# electrophy_RHD.net
KiCad netlist of a schematic drawn in EAGLE
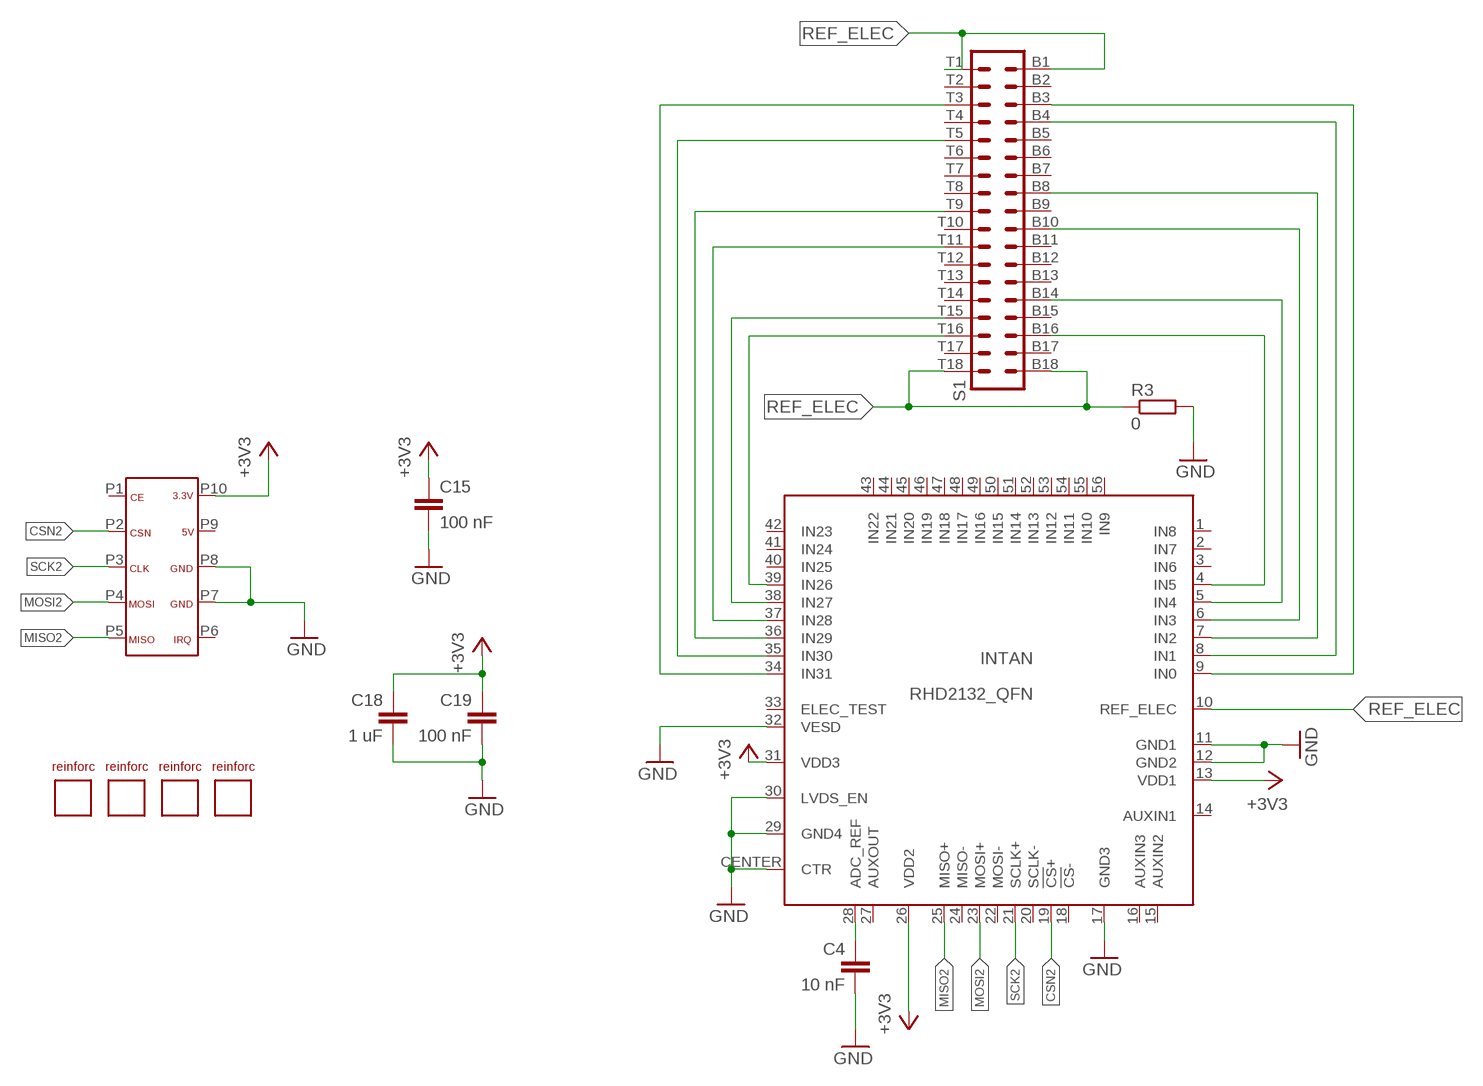
[diagram p0: schematic, sheet 1]

(export (version "E")
  (design (tool "Eeschema 10.0.6"))
  (components
    (comp (ref "C4")
      (value "10 nF")
      (footprint "eagle-import:C0603")
      (libsource (lib "eagle-import") (part "C-EUC0603"))
    )
    (comp (ref "C15")
      (value "100 nF")
      (footprint "eagle-import:C0603")
      (libsource (lib "eagle-import") (part "C-EUC0603"))
    )
    (comp (ref "C18")
      (value "1 uF")
      (footprint "eagle-import:C0603")
      (libsource (lib "eagle-import") (part "C-EUC0603"))
    )
    (comp (ref "C19")
      (value "100 nF")
      (footprint "eagle-import:C0603")
      (libsource (lib "eagle-import") (part "C-EUC0603"))
    )
    (comp (ref "INTAN")
      (value "RHD2132_QFN")
      (footprint "eagle-import:QFN56_8_X_8_LARGE")
      (libsource (lib "eagle-import") (part "RHD2132_QFN"))
    )
    (comp (ref "R3")
      (value "0")
      (footprint "eagle-import:R0603")
      (libsource (lib "eagle-import") (part "R-EU_R0603"))
    )
    (comp (ref "S1")
      (value "OMNETICS_A79027")
      (footprint "eagle-import:OMNETICS_A79027")
      (libsource (lib "eagle-import") (part "OMNETICS_A79027"))
    )
    (comp (ref "U$1")
      (value "DF12-10-FEMALE")
      (footprint "eagle-import:DF12-10-FEMALE")
      (libsource (lib "eagle-import") (part "DF12-10-FEMALE"))
    )
    (comp (ref "U$2")
      (value "REINFORCEMENT")
      (footprint "eagle-import:REINFORCEMENT")
      (libsource (lib "eagle-import") (part "REINFORCEMENT"))
    )
    (comp (ref "U$3")
      (value "REINFORCEMENT")
      (footprint "eagle-import:REINFORCEMENT")
      (libsource (lib "eagle-import") (part "REINFORCEMENT"))
    )
    (comp (ref "U$4")
      (value "REINFORCEMENT")
      (footprint "eagle-import:REINFORCEMENT")
      (libsource (lib "eagle-import") (part "REINFORCEMENT"))
    )
    (comp (ref "U$5")
      (value "REINFORCEMENT")
      (footprint "eagle-import:REINFORCEMENT")
      (libsource (lib "eagle-import") (part "REINFORCEMENT"))
    )
  )
  (nets
    (net (code "1") (name "+3V3") (class "Default")
      (node (ref "C15") (pin "1") (pinfunction "1_1") (pintype "passive"))
      (node (ref "C18") (pin "1") (pinfunction "1_1") (pintype "passive"))
      (node (ref "C19") (pin "1") (pinfunction "1_1") (pintype "passive"))
      (node (ref "INTAN") (pin "13") (pinfunction "VDD1_13") (pintype "bidirectional"))
      (node (ref "INTAN") (pin "26") (pinfunction "VDD2_26") (pintype "bidirectional"))
      (node (ref "INTAN") (pin "31") (pinfunction "VDD3_31") (pintype "bidirectional"))
      (node (ref "U$1") (pin "P10") (pinfunction "P10_P10") (pintype "passive"))
    )
    (net (code "2") (name "CSN2") (class "Default")
      (node (ref "INTAN") (pin "19") (pinfunction "~{CS}+_19") (pintype "bidirectional"))
      (node (ref "U$1") (pin "P2") (pinfunction "P2_P2") (pintype "passive"))
    )
    (net (code "3") (name "GND") (class "Default")
      (node (ref "C15") (pin "2") (pinfunction "2_2") (pintype "passive"))
      (node (ref "C18") (pin "2") (pinfunction "2_2") (pintype "passive"))
      (node (ref "C19") (pin "2") (pinfunction "2_2") (pintype "passive"))
      (node (ref "C4") (pin "2") (pinfunction "2_2") (pintype "passive"))
      (node (ref "INTAN") (pin "11") (pinfunction "GND1_11") (pintype "bidirectional"))
      (node (ref "INTAN") (pin "12") (pinfunction "GND2_12") (pintype "bidirectional"))
      (node (ref "INTAN") (pin "17") (pinfunction "GND3_17") (pintype "bidirectional"))
      (node (ref "INTAN") (pin "29") (pinfunction "GND4_29") (pintype "bidirectional"))
      (node (ref "INTAN") (pin "30") (pinfunction "LVDS_EN_30") (pintype "bidirectional"))
      (node (ref "INTAN") (pin "32") (pinfunction "VESD_32") (pintype "bidirectional"))
      (node (ref "INTAN") (pin "CENTER") (pinfunction "CTR_CENTER") (pintype "bidirectional"))
      (node (ref "R3") (pin "2") (pinfunction "2_2") (pintype "passive"))
      (node (ref "U$1") (pin "P7") (pinfunction "P7_P7") (pintype "passive"))
      (node (ref "U$1") (pin "P8") (pinfunction "P8_P8") (pintype "passive"))
    )
    (net (code "4") (name "MISO2") (class "Default")
      (node (ref "INTAN") (pin "25") (pinfunction "MISO+_25") (pintype "bidirectional"))
      (node (ref "U$1") (pin "P5") (pinfunction "P5_P5") (pintype "passive"))
    )
    (net (code "5") (name "MOSI2") (class "Default")
      (node (ref "INTAN") (pin "23") (pinfunction "MOSI+_23") (pintype "bidirectional"))
      (node (ref "U$1") (pin "P4") (pinfunction "P4_P4") (pintype "passive"))
    )
    (net (code "6") (name "Net-(INTAN-ADC_REF)") (class "Default")
      (node (ref "C4") (pin "1") (pinfunction "1_1") (pintype "passive"))
      (node (ref "INTAN") (pin "28") (pinfunction "ADC_REF_28") (pintype "bidirectional"))
    )
    (net (code "7") (name "Net-(INTAN-IN0)") (class "Default")
      (node (ref "INTAN") (pin "9") (pinfunction "IN0_9") (pintype "bidirectional"))
      (node (ref "S1") (pin "B3") (pinfunction "B3_B3") (pintype "passive"))
    )
    (net (code "8") (name "Net-(INTAN-IN1)") (class "Default")
      (node (ref "INTAN") (pin "8") (pinfunction "IN1_8") (pintype "bidirectional"))
      (node (ref "S1") (pin "B4") (pinfunction "B4_B4") (pintype "passive"))
    )
    (net (code "9") (name "Net-(INTAN-IN2)") (class "Default")
      (node (ref "INTAN") (pin "7") (pinfunction "IN2_7") (pintype "bidirectional"))
      (node (ref "S1") (pin "B8") (pinfunction "B8_B8") (pintype "passive"))
    )
    (net (code "10") (name "Net-(INTAN-IN3)") (class "Default")
      (node (ref "INTAN") (pin "6") (pinfunction "IN3_6") (pintype "bidirectional"))
      (node (ref "S1") (pin "B10") (pinfunction "B10_B10") (pintype "passive"))
    )
    (net (code "11") (name "Net-(INTAN-IN4)") (class "Default")
      (node (ref "INTAN") (pin "5") (pinfunction "IN4_5") (pintype "bidirectional"))
      (node (ref "S1") (pin "B14") (pinfunction "B14_B14") (pintype "passive"))
    )
    (net (code "12") (name "Net-(INTAN-IN5)") (class "Default")
      (node (ref "INTAN") (pin "4") (pinfunction "IN5_4") (pintype "bidirectional"))
      (node (ref "S1") (pin "B16") (pinfunction "B16_B16") (pintype "passive"))
    )
    (net (code "13") (name "Net-(INTAN-IN26)") (class "Default")
      (node (ref "INTAN") (pin "39") (pinfunction "IN26_39") (pintype "bidirectional"))
      (node (ref "S1") (pin "T16") (pinfunction "T16_T16") (pintype "passive"))
    )
    (net (code "14") (name "Net-(INTAN-IN27)") (class "Default")
      (node (ref "INTAN") (pin "38") (pinfunction "IN27_38") (pintype "bidirectional"))
      (node (ref "S1") (pin "T15") (pinfunction "T15_T15") (pintype "passive"))
    )
    (net (code "15") (name "Net-(INTAN-IN28)") (class "Default")
      (node (ref "INTAN") (pin "37") (pinfunction "IN28_37") (pintype "bidirectional"))
      (node (ref "S1") (pin "T11") (pinfunction "T11_T11") (pintype "passive"))
    )
    (net (code "16") (name "Net-(INTAN-IN29)") (class "Default")
      (node (ref "INTAN") (pin "36") (pinfunction "IN29_36") (pintype "bidirectional"))
      (node (ref "S1") (pin "T9") (pinfunction "T9_T9") (pintype "passive"))
    )
    (net (code "17") (name "Net-(INTAN-IN30)") (class "Default")
      (node (ref "INTAN") (pin "35") (pinfunction "IN30_35") (pintype "bidirectional"))
      (node (ref "S1") (pin "T5") (pinfunction "T5_T5") (pintype "passive"))
    )
    (net (code "18") (name "Net-(INTAN-IN31)") (class "Default")
      (node (ref "INTAN") (pin "34") (pinfunction "IN31_34") (pintype "bidirectional"))
      (node (ref "S1") (pin "T3") (pinfunction "T3_T3") (pintype "passive"))
    )
    (net (code "19") (name "REF_ELEC") (class "Default")
      (node (ref "INTAN") (pin "10") (pinfunction "REF_ELEC_10") (pintype "input"))
      (node (ref "R3") (pin "1") (pinfunction "1_1") (pintype "passive"))
      (node (ref "S1") (pin "B1") (pinfunction "B1_B1") (pintype "passive"))
      (node (ref "S1") (pin "B18") (pinfunction "B18_B18") (pintype "passive"))
      (node (ref "S1") (pin "T1") (pinfunction "T1_T1") (pintype "passive"))
      (node (ref "S1") (pin "T18") (pinfunction "T18_T18") (pintype "passive"))
    )
    (net (code "20") (name "SCK2") (class "Default")
      (node (ref "INTAN") (pin "21") (pinfunction "SCLK+_21") (pintype "bidirectional"))
      (node (ref "U$1") (pin "P3") (pinfunction "P3_P3") (pintype "passive"))
    )
    (net (code "21") (name "unconnected-(INTAN-AUXIN1-Pad14)") (class "Default")
      (node (ref "INTAN") (pin "14") (pinfunction "AUXIN1_14") (pintype "bidirectional"))
    )
    (net (code "22") (name "unconnected-(INTAN-AUXIN2-Pad15)") (class "Default")
      (node (ref "INTAN") (pin "15") (pinfunction "AUXIN2_15") (pintype "bidirectional"))
    )
    (net (code "23") (name "unconnected-(INTAN-AUXIN3-Pad16)") (class "Default")
      (node (ref "INTAN") (pin "16") (pinfunction "AUXIN3_16") (pintype "bidirectional"))
    )
    (net (code "24") (name "unconnected-(INTAN-AUXOUT-Pad27)") (class "Default")
      (node (ref "INTAN") (pin "27") (pinfunction "AUXOUT_27") (pintype "bidirectional"))
    )
    (net (code "25") (name "unconnected-(INTAN-ELEC_TEST-Pad33)") (class "Default")
      (node (ref "INTAN") (pin "33") (pinfunction "ELEC_TEST_33") (pintype "bidirectional"))
    )
    (net (code "26") (name "unconnected-(INTAN-IN6-Pad3)") (class "Default")
      (node (ref "INTAN") (pin "3") (pinfunction "IN6_3") (pintype "bidirectional"))
    )
    (net (code "27") (name "unconnected-(INTAN-IN7-Pad2)") (class "Default")
      (node (ref "INTAN") (pin "2") (pinfunction "IN7_2") (pintype "bidirectional"))
    )
    (net (code "28") (name "unconnected-(INTAN-IN8-Pad1)") (class "Default")
      (node (ref "INTAN") (pin "1") (pinfunction "IN8_1") (pintype "bidirectional"))
    )
    (net (code "29") (name "unconnected-(INTAN-IN9-Pad56)") (class "Default")
      (node (ref "INTAN") (pin "56") (pinfunction "IN9_56") (pintype "bidirectional"))
    )
    (net (code "30") (name "unconnected-(INTAN-IN10-Pad55)") (class "Default")
      (node (ref "INTAN") (pin "55") (pinfunction "IN10_55") (pintype "bidirectional"))
    )
    (net (code "31") (name "unconnected-(INTAN-IN11-Pad54)") (class "Default")
      (node (ref "INTAN") (pin "54") (pinfunction "IN11_54") (pintype "bidirectional"))
    )
    (net (code "32") (name "unconnected-(INTAN-IN12-Pad53)") (class "Default")
      (node (ref "INTAN") (pin "53") (pinfunction "IN12_53") (pintype "bidirectional"))
    )
    (net (code "33") (name "unconnected-(INTAN-IN13-Pad52)") (class "Default")
      (node (ref "INTAN") (pin "52") (pinfunction "IN13_52") (pintype "bidirectional"))
    )
    (net (code "34") (name "unconnected-(INTAN-IN14-Pad51)") (class "Default")
      (node (ref "INTAN") (pin "51") (pinfunction "IN14_51") (pintype "bidirectional"))
    )
    (net (code "35") (name "unconnected-(INTAN-IN15-Pad50)") (class "Default")
      (node (ref "INTAN") (pin "50") (pinfunction "IN15_50") (pintype "bidirectional"))
    )
    (net (code "36") (name "unconnected-(INTAN-IN16-Pad49)") (class "Default")
      (node (ref "INTAN") (pin "49") (pinfunction "IN16_49") (pintype "bidirectional"))
    )
    (net (code "37") (name "unconnected-(INTAN-IN17-Pad48)") (class "Default")
      (node (ref "INTAN") (pin "48") (pinfunction "IN17_48") (pintype "bidirectional"))
    )
    (net (code "38") (name "unconnected-(INTAN-IN18-Pad47)") (class "Default")
      (node (ref "INTAN") (pin "47") (pinfunction "IN18_47") (pintype "bidirectional"))
    )
    (net (code "39") (name "unconnected-(INTAN-IN19-Pad46)") (class "Default")
      (node (ref "INTAN") (pin "46") (pinfunction "IN19_46") (pintype "bidirectional"))
    )
    (net (code "40") (name "unconnected-(INTAN-IN20-Pad45)") (class "Default")
      (node (ref "INTAN") (pin "45") (pinfunction "IN20_45") (pintype "bidirectional"))
    )
    (net (code "41") (name "unconnected-(INTAN-IN21-Pad44)") (class "Default")
      (node (ref "INTAN") (pin "44") (pinfunction "IN21_44") (pintype "bidirectional"))
    )
    (net (code "42") (name "unconnected-(INTAN-IN22-Pad43)") (class "Default")
      (node (ref "INTAN") (pin "43") (pinfunction "IN22_43") (pintype "bidirectional"))
    )
    (net (code "43") (name "unconnected-(INTAN-IN23-Pad42)") (class "Default")
      (node (ref "INTAN") (pin "42") (pinfunction "IN23_42") (pintype "bidirectional"))
    )
    (net (code "44") (name "unconnected-(INTAN-IN24-Pad41)") (class "Default")
      (node (ref "INTAN") (pin "41") (pinfunction "IN24_41") (pintype "bidirectional"))
    )
    (net (code "45") (name "unconnected-(INTAN-IN25-Pad40)") (class "Default")
      (node (ref "INTAN") (pin "40") (pinfunction "IN25_40") (pintype "bidirectional"))
    )
    (net (code "46") (name "unconnected-(INTAN-MISO--Pad24)") (class "Default")
      (node (ref "INTAN") (pin "24") (pinfunction "MISO-_24") (pintype "bidirectional"))
    )
    (net (code "47") (name "unconnected-(INTAN-MOSI--Pad22)") (class "Default")
      (node (ref "INTAN") (pin "22") (pinfunction "MOSI-_22") (pintype "bidirectional"))
    )
    (net (code "48") (name "unconnected-(INTAN-SCLK--Pad20)") (class "Default")
      (node (ref "INTAN") (pin "20") (pinfunction "SCLK-_20") (pintype "bidirectional"))
    )
    (net (code "49") (name "unconnected-(INTAN-~{CS}--Pad18)") (class "Default")
      (node (ref "INTAN") (pin "18") (pinfunction "~{CS}-_18") (pintype "bidirectional"))
    )
    (net (code "50") (name "unconnected-(S1-PadB2)") (class "Default")
      (node (ref "S1") (pin "B2") (pinfunction "B2_B2") (pintype "passive"))
    )
    (net (code "51") (name "unconnected-(S1-PadB5)") (class "Default")
      (node (ref "S1") (pin "B5") (pinfunction "B5_B5") (pintype "passive"))
    )
    (net (code "52") (name "unconnected-(S1-PadB6)") (class "Default")
      (node (ref "S1") (pin "B6") (pinfunction "B6_B6") (pintype "passive"))
    )
    (net (code "53") (name "unconnected-(S1-PadB7)") (class "Default")
      (node (ref "S1") (pin "B7") (pinfunction "B7_B7") (pintype "passive"))
    )
    (net (code "54") (name "unconnected-(S1-PadB9)") (class "Default")
      (node (ref "S1") (pin "B9") (pinfunction "B9_B9") (pintype "passive"))
    )
    (net (code "55") (name "unconnected-(S1-PadB11)") (class "Default")
      (node (ref "S1") (pin "B11") (pinfunction "B11_B11") (pintype "passive"))
    )
    (net (code "56") (name "unconnected-(S1-PadB12)") (class "Default")
      (node (ref "S1") (pin "B12") (pinfunction "B12_B12") (pintype "passive"))
    )
    (net (code "57") (name "unconnected-(S1-PadB13)") (class "Default")
      (node (ref "S1") (pin "B13") (pinfunction "B13_B13") (pintype "passive"))
    )
    (net (code "58") (name "unconnected-(S1-PadB15)") (class "Default")
      (node (ref "S1") (pin "B15") (pinfunction "B15_B15") (pintype "passive"))
    )
    (net (code "59") (name "unconnected-(S1-PadB17)") (class "Default")
      (node (ref "S1") (pin "B17") (pinfunction "B17_B17") (pintype "passive"))
    )
    (net (code "60") (name "unconnected-(S1-PadT2)") (class "Default")
      (node (ref "S1") (pin "T2") (pinfunction "T2_T2") (pintype "passive"))
    )
    (net (code "61") (name "unconnected-(S1-PadT4)") (class "Default")
      (node (ref "S1") (pin "T4") (pinfunction "T4_T4") (pintype "passive"))
    )
    (net (code "62") (name "unconnected-(S1-PadT6)") (class "Default")
      (node (ref "S1") (pin "T6") (pinfunction "T6_T6") (pintype "passive"))
    )
    (net (code "63") (name "unconnected-(S1-PadT7)") (class "Default")
      (node (ref "S1") (pin "T7") (pinfunction "T7_T7") (pintype "passive"))
    )
    (net (code "64") (name "unconnected-(S1-PadT8)") (class "Default")
      (node (ref "S1") (pin "T8") (pinfunction "T8_T8") (pintype "passive"))
    )
    (net (code "65") (name "unconnected-(S1-PadT10)") (class "Default")
      (node (ref "S1") (pin "T10") (pinfunction "T10_T10") (pintype "passive"))
    )
    (net (code "66") (name "unconnected-(S1-PadT12)") (class "Default")
      (node (ref "S1") (pin "T12") (pinfunction "T12_T12") (pintype "passive"))
    )
    (net (code "67") (name "unconnected-(S1-PadT13)") (class "Default")
      (node (ref "S1") (pin "T13") (pinfunction "T13_T13") (pintype "passive"))
    )
    (net (code "68") (name "unconnected-(S1-PadT14)") (class "Default")
      (node (ref "S1") (pin "T14") (pinfunction "T14_T14") (pintype "passive"))
    )
    (net (code "69") (name "unconnected-(S1-PadT17)") (class "Default")
      (node (ref "S1") (pin "T17") (pinfunction "T17_T17") (pintype "passive"))
    )
    (net (code "70") (name "unconnected-(U$1-PadP1)") (class "Default")
      (node (ref "U$1") (pin "P1") (pinfunction "P1_P1") (pintype "passive"))
    )
    (net (code "71") (name "unconnected-(U$1-PadP6)") (class "Default")
      (node (ref "U$1") (pin "P6") (pinfunction "P6_P6") (pintype "passive"))
    )
    (net (code "72") (name "unconnected-(U$1-PadP9)") (class "Default")
      (node (ref "U$1") (pin "P9") (pinfunction "P9_P9") (pintype "passive"))
    )
    (net (code "73") (name "unconnected-(U$2-PadP$1)") (class "Default")
      (node (ref "U$2") (pin "P$1") (pinfunction "P$1_P$1") (pintype "bidirectional"))
    )
    (net (code "74") (name "unconnected-(U$3-PadP$1)") (class "Default")
      (node (ref "U$3") (pin "P$1") (pinfunction "P$1_P$1") (pintype "bidirectional"))
    )
    (net (code "75") (name "unconnected-(U$4-PadP$1)") (class "Default")
      (node (ref "U$4") (pin "P$1") (pinfunction "P$1_P$1") (pintype "bidirectional"))
    )
    (net (code "76") (name "unconnected-(U$5-PadP$1)") (class "Default")
      (node (ref "U$5") (pin "P$1") (pinfunction "P$1_P$1") (pintype "bidirectional"))
    )
  )
)
